# Interfaces_Isolation.net
KiCad netlist of a schematic drawn in Altium Designer
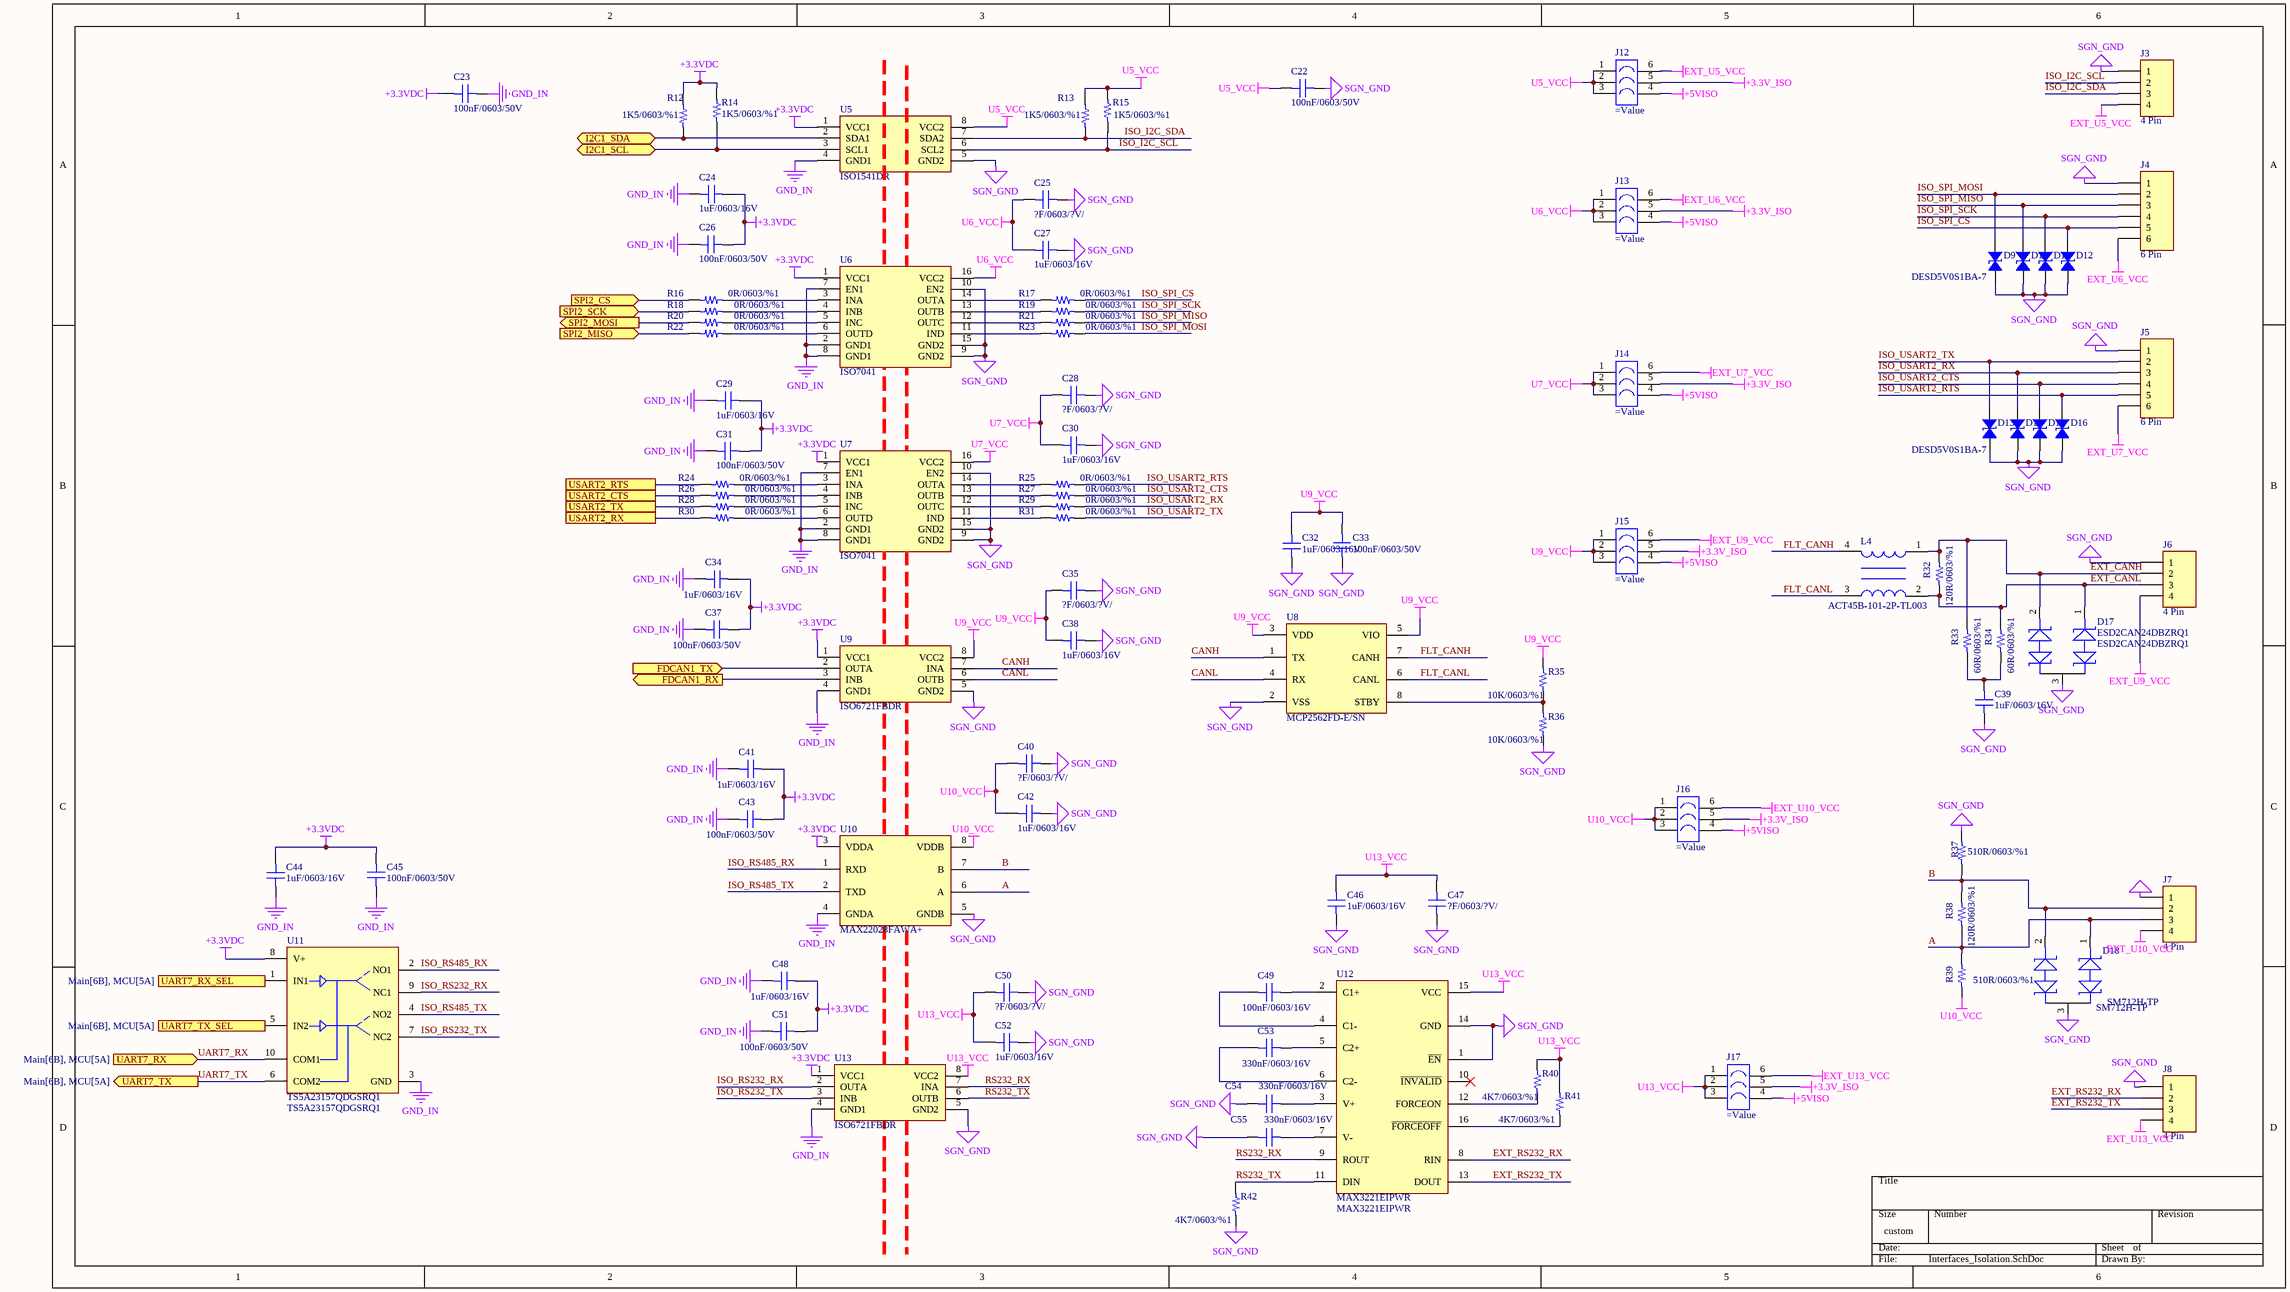
[diagram p0: Interfaces_Isolation.SchDoc]

(export (version "E")
  (design (tool "Eeschema 10.0.6"))
  (components
    (comp (ref "C22")
      (value "100nF/0603/50V")
      (footprint "0603_cap")
      (libsource (lib "IM_v1.0") (part "Capacitor"))
    )
    (comp (ref "C23")
      (value "100nF/0603/50V")
      (footprint "0603_cap")
      (libsource (lib "IM_v1.0") (part "Capacitor"))
    )
    (comp (ref "C24")
      (value "1uF/0603/16V")
      (footprint "0603_cap")
      (libsource (lib "IM_v1.0") (part "Capacitor"))
    )
    (comp (ref "C25")
      (value "?F/0603/?V/")
      (footprint "0603_cap")
      (libsource (lib "IM_v1.0") (part "Capacitor"))
    )
    (comp (ref "C26")
      (value "100nF/0603/50V")
      (footprint "0603_cap")
      (libsource (lib "IM_v1.0") (part "Capacitor"))
    )
    (comp (ref "C27")
      (value "1uF/0603/16V")
      (footprint "0603_cap")
      (libsource (lib "IM_v1.0") (part "Capacitor"))
    )
    (comp (ref "C28")
      (value "?F/0603/?V/")
      (footprint "0603_cap")
      (libsource (lib "IM_v1.0") (part "Capacitor"))
    )
    (comp (ref "C29")
      (value "1uF/0603/16V")
      (footprint "0603_cap")
      (libsource (lib "IM_v1.0") (part "Capacitor"))
    )
    (comp (ref "C30")
      (value "1uF/0603/16V")
      (footprint "0603_cap")
      (libsource (lib "IM_v1.0") (part "Capacitor"))
    )
    (comp (ref "C31")
      (value "100nF/0603/50V")
      (footprint "0603_cap")
      (libsource (lib "IM_v1.0") (part "Capacitor"))
    )
    (comp (ref "C32")
      (value "1uF/0603/16V")
      (footprint "0603_cap")
      (libsource (lib "IM_v1.0") (part "Capacitor"))
    )
    (comp (ref "C33")
      (value "100nF/0603/50V")
      (footprint "0603_cap")
      (libsource (lib "IM_v1.0") (part "Capacitor"))
    )
    (comp (ref "C34")
      (value "1uF/0603/16V")
      (footprint "0603_cap")
      (libsource (lib "IM_v1.0") (part "Capacitor"))
    )
    (comp (ref "C35")
      (value "?F/0603/?V/")
      (footprint "0603_cap")
      (libsource (lib "IM_v1.0") (part "Capacitor"))
    )
    (comp (ref "C37")
      (value "100nF/0603/50V")
      (footprint "0603_cap")
      (libsource (lib "IM_v1.0") (part "Capacitor"))
    )
    (comp (ref "C38")
      (value "1uF/0603/16V")
      (footprint "0603_cap")
      (libsource (lib "IM_v1.0") (part "Capacitor"))
    )
    (comp (ref "C39")
      (value "1uF/0603/16V")
      (footprint "0603_cap")
      (libsource (lib "IM_v1.0") (part "Capacitor"))
    )
    (comp (ref "C40")
      (value "?F/0603/?V/")
      (footprint "0603_cap")
      (libsource (lib "IM_v1.0") (part "Capacitor"))
    )
    (comp (ref "C41")
      (value "1uF/0603/16V")
      (footprint "0603_cap")
      (libsource (lib "IM_v1.0") (part "Capacitor"))
    )
    (comp (ref "C42")
      (value "1uF/0603/16V")
      (footprint "0603_cap")
      (libsource (lib "IM_v1.0") (part "Capacitor"))
    )
    (comp (ref "C43")
      (value "100nF/0603/50V")
      (footprint "0603_cap")
      (libsource (lib "IM_v1.0") (part "Capacitor"))
    )
    (comp (ref "C44")
      (value "1uF/0603/16V")
      (footprint "0603_cap")
      (libsource (lib "IM_v1.0") (part "Capacitor"))
    )
    (comp (ref "C45")
      (value "100nF/0603/50V")
      (footprint "0603_cap")
      (libsource (lib "IM_v1.0") (part "Capacitor"))
    )
    (comp (ref "C46")
      (value "1uF/0603/16V")
      (footprint "0603_cap")
      (libsource (lib "IM_v1.0") (part "Capacitor"))
    )
    (comp (ref "C47")
      (value "?F/0603/?V/")
      (footprint "0603_cap")
      (libsource (lib "IM_v1.0") (part "Capacitor"))
    )
    (comp (ref "C48")
      (value "1uF/0603/16V")
      (footprint "0603_cap")
      (libsource (lib "IM_v1.0") (part "Capacitor"))
    )
    (comp (ref "C49")
      (value "100nF/0603/16V")
      (footprint "0603_cap")
      (libsource (lib "IM_v1.0") (part "Capacitor"))
    )
    (comp (ref "C50")
      (value "?F/0603/?V/")
      (footprint "0603_cap")
      (libsource (lib "IM_v1.0") (part "Capacitor"))
    )
    (comp (ref "C51")
      (value "100nF/0603/50V")
      (footprint "0603_cap")
      (libsource (lib "IM_v1.0") (part "Capacitor"))
    )
    (comp (ref "C52")
      (value "1uF/0603/16V")
      (footprint "0603_cap")
      (libsource (lib "IM_v1.0") (part "Capacitor"))
    )
    (comp (ref "C53")
      (value "330nF/0603/16V")
      (footprint "0603_cap")
      (libsource (lib "IM_v1.0") (part "Capacitor"))
    )
    (comp (ref "C54")
      (value "330nF/0603/16V")
      (footprint "0603_cap")
      (libsource (lib "IM_v1.0") (part "Capacitor"))
    )
    (comp (ref "C55")
      (value "330nF/0603/16V")
      (footprint "0603_cap")
      (libsource (lib "IM_v1.0") (part "Capacitor"))
    )
    (comp (ref "D9")
      (value "DESD5V0S1BA-7")
      (footprint "SOD323")
      (description "Zener Diode")
      (libsource (lib "IM_v1.0") (part "TVS BI"))
    )
    (comp (ref "D10")
      (value "DESD5V0S1BA-7")
      (footprint "SOD323")
      (description "Zener Diode")
      (libsource (lib "IM_v1.0") (part "TVS BI"))
    )
    (comp (ref "D11")
      (value "DESD5V0S1BA-7")
      (footprint "SOD323")
      (description "Zener Diode")
      (libsource (lib "IM_v1.0") (part "TVS BI"))
    )
    (comp (ref "D12")
      (value "DESD5V0S1BA-7")
      (footprint "SOD323")
      (description "Zener Diode")
      (libsource (lib "IM_v1.0") (part "TVS BI"))
    )
    (comp (ref "D13")
      (value "DESD5V0S1BA-7")
      (footprint "SOD323")
      (description "Zener Diode")
      (libsource (lib "IM_v1.0") (part "TVS BI"))
    )
    (comp (ref "D14")
      (value "DESD5V0S1BA-7")
      (footprint "SOD323")
      (description "Zener Diode")
      (libsource (lib "IM_v1.0") (part "TVS BI"))
    )
    (comp (ref "D15")
      (value "DESD5V0S1BA-7")
      (footprint "SOD323")
      (description "Zener Diode")
      (libsource (lib "IM_v1.0") (part "TVS BI"))
    )
    (comp (ref "D16")
      (value "DESD5V0S1BA-7")
      (footprint "SOD323")
      (description "Zener Diode")
      (libsource (lib "IM_v1.0") (part "TVS BI"))
    )
    (comp (ref "D17")
      (value "ESD2CAN24DBZRQ1")
      (footprint "TI SOT-23-3 DBZ")
      (description "37V (Typ) Clamp 5.7A (8/20µs) Ipp Tvs Diode Surface Mount SOT-23-3")
      (fields (field (name "ALTIUM_VALUE") "ESD2CAN24DBZRQ1"))
      (libsource (lib "IM_v1.0") (part "SM712H-TP"))
    )
    (comp (ref "D18")
      (value "SM712H-TP")
      (footprint "TI SOT-23-3 DBZ")
      (description "TVS DIODE 12VWM 28VC SOT23")
      (fields (field (name "ALTIUM_VALUE") "SM712H-TP"))
      (libsource (lib "IM_v1.0") (part "SM712H-TP"))
    )
    (comp (ref "J3")
      (value "4 Pin")
      (footprint "R/A HEADER (4PİN)")
      (libsource (lib "IM_v1.0") (part "4 Pin"))
    )
    (comp (ref "J4") (value "6 Pin") (footprint "R/A HEADER") (libsource (lib "IM_v1.0") (part "6 Pin")))
    (comp (ref "J5") (value "6 Pin") (footprint "R/A HEADER") (libsource (lib "IM_v1.0") (part "6 Pin")))
    (comp (ref "J6")
      (value "4 Pin")
      (footprint "R/A HEADER (4PİN)")
      (libsource (lib "IM_v1.0") (part "4 Pin"))
    )
    (comp (ref "J7")
      (value "4 Pin")
      (footprint "R/A HEADER (4PİN)")
      (libsource (lib "IM_v1.0") (part "4 Pin"))
    )
    (comp (ref "J8")
      (value "4 Pin")
      (footprint "R/A HEADER (4PİN)")
      (libsource (lib "IM_v1.0") (part "4 Pin"))
    )
    (comp (ref "J12")
      (value "~")
      (footprint "th_ra_6pins_1.27mm")
      (libsource (lib "IM_v1.0") (part "2x3_header"))
    )
    (comp (ref "J13")
      (value "~")
      (footprint "th_ra_6pins_1.27mm")
      (libsource (lib "IM_v1.0") (part "2x3_header"))
    )
    (comp (ref "J14")
      (value "~")
      (footprint "th_ra_6pins_1.27mm")
      (libsource (lib "IM_v1.0") (part "2x3_header"))
    )
    (comp (ref "J15")
      (value "~")
      (footprint "th_ra_6pins_1.27mm")
      (libsource (lib "IM_v1.0") (part "2x3_header"))
    )
    (comp (ref "J16")
      (value "~")
      (footprint "th_ra_6pins_1.27mm")
      (libsource (lib "IM_v1.0") (part "2x3_header"))
    )
    (comp (ref "J17")
      (value "~")
      (footprint "th_ra_6pins_1.27mm")
      (libsource (lib "IM_v1.0") (part "2x3_header"))
    )
    (comp (ref "L4")
      (value "ACT45B-101-2P-TL003")
      (footprint "CMC((4.50mm x 3.20mm))")
      (description "100 µH @ 100 kHz 2 Line Common Mode Choke Surface Mount 5.8 kOhms @ 10 MHz 150mA DCR 2Ohm")
      (libsource (lib "IM_v1.0") (part "cmc"))
    )
    (comp (ref "R12") (value "1K5/0603/%1") (footprint "0603_res") (libsource (lib "IM_v1.0") (part "RES")))
    (comp (ref "R13") (value "1K5/0603/%1") (footprint "0603_res") (libsource (lib "IM_v1.0") (part "RES")))
    (comp (ref "R14") (value "1K5/0603/%1") (footprint "0603_res") (libsource (lib "IM_v1.0") (part "RES")))
    (comp (ref "R15") (value "1K5/0603/%1") (footprint "0603_res") (libsource (lib "IM_v1.0") (part "RES")))
    (comp (ref "R16") (value "0R/0603/%1") (footprint "0603_res") (libsource (lib "IM_v1.0") (part "RES")))
    (comp (ref "R17") (value "0R/0603/%1") (footprint "0603_res") (libsource (lib "IM_v1.0") (part "RES")))
    (comp (ref "R18") (value "0R/0603/%1") (footprint "0603_res") (libsource (lib "IM_v1.0") (part "RES")))
    (comp (ref "R19") (value "0R/0603/%1") (footprint "0603_res") (libsource (lib "IM_v1.0") (part "RES")))
    (comp (ref "R20") (value "0R/0603/%1") (footprint "0603_res") (libsource (lib "IM_v1.0") (part "RES")))
    (comp (ref "R21") (value "0R/0603/%1") (footprint "0603_res") (libsource (lib "IM_v1.0") (part "RES")))
    (comp (ref "R22") (value "0R/0603/%1") (footprint "0603_res") (libsource (lib "IM_v1.0") (part "RES")))
    (comp (ref "R23") (value "0R/0603/%1") (footprint "0603_res") (libsource (lib "IM_v1.0") (part "RES")))
    (comp (ref "R24") (value "0R/0603/%1") (footprint "0603_res") (libsource (lib "IM_v1.0") (part "RES")))
    (comp (ref "R25") (value "0R/0603/%1") (footprint "0603_res") (libsource (lib "IM_v1.0") (part "RES")))
    (comp (ref "R26") (value "0R/0603/%1") (footprint "0603_res") (libsource (lib "IM_v1.0") (part "RES")))
    (comp (ref "R27") (value "0R/0603/%1") (footprint "0603_res") (libsource (lib "IM_v1.0") (part "RES")))
    (comp (ref "R28") (value "0R/0603/%1") (footprint "0603_res") (libsource (lib "IM_v1.0") (part "RES")))
    (comp (ref "R29") (value "0R/0603/%1") (footprint "0603_res") (libsource (lib "IM_v1.0") (part "RES")))
    (comp (ref "R30") (value "0R/0603/%1") (footprint "0603_res") (libsource (lib "IM_v1.0") (part "RES")))
    (comp (ref "R31") (value "0R/0603/%1") (footprint "0603_res") (libsource (lib "IM_v1.0") (part "RES")))
    (comp (ref "R32") (value "120R/0603/%1") (footprint "0603_res") (libsource (lib "IM_v1.0") (part "RES")))
    (comp (ref "R33") (value "60R/0603/%1") (footprint "0603_res") (libsource (lib "IM_v1.0") (part "RES")))
    (comp (ref "R34") (value "60R/0603/%1") (footprint "0603_res") (libsource (lib "IM_v1.0") (part "RES")))
    (comp (ref "R35") (value "10K/0603/%1") (footprint "0603_res") (libsource (lib "IM_v1.0") (part "RES")))
    (comp (ref "R36") (value "10K/0603/%1") (footprint "0603_res") (libsource (lib "IM_v1.0") (part "RES")))
    (comp (ref "R37") (value "510R/0603/%1") (footprint "0603_res") (libsource (lib "IM_v1.0") (part "RES")))
    (comp (ref "R38") (value "120R/0603/%1") (footprint "0603_res") (libsource (lib "IM_v1.0") (part "RES")))
    (comp (ref "R39") (value "510R/0603/%1") (footprint "0603_res") (libsource (lib "IM_v1.0") (part "RES")))
    (comp (ref "R40") (value "4K7/0603/%1") (footprint "0603_res") (libsource (lib "IM_v1.0") (part "RES")))
    (comp (ref "R41") (value "4K7/0603/%1") (footprint "0603_res") (libsource (lib "IM_v1.0") (part "RES")))
    (comp (ref "R42") (value "4K7/0603/%1") (footprint "0603_res") (libsource (lib "IM_v1.0") (part "RES")))
    (comp (ref "U5")
      (value "ISO1541DR")
      (footprint "SOIC-8(3.90MM)")
      (description "I2C Digital Isolator 2500Vrms 2 Channel 1Mbps 25kV/µs CMTI 8-SOIC (0.154\", 3.90mm Width)")
      (libsource (lib "IM_v1.0") (part "TI ISO154x"))
    )
    (comp (ref "U6")
      (value "ISO7041")
      (footprint "16-SSOP (0.154\", 3.90mm Width)")
      (description "SPI Digital Isolator 3000Vrms 4 Channel 2Mbps 50kV/µs CMTI 16-SSOP (0.154\", 3.90mm Width)")
      (libsource (lib "IM_v1.0") (part "ISO7041"))
    )
    (comp (ref "U7")
      (value "ISO7041")
      (footprint "16-SSOP (0.154\", 3.90mm Width)")
      (description "SPI Digital Isolator 3000Vrms 4 Channel 2Mbps 50kV/µs CMTI 16-SSOP (0.154\", 3.90mm Width)")
      (libsource (lib "IM_v1.0") (part "ISO7041"))
    )
    (comp (ref "U8")
      (value "MCP2562FD-E/SN")
      (footprint "SOIC-8(3.90MM)")
      (description "1/1 Transceiver CANbus 8-SOIC")
      (libsource (lib "IM_v1.0") (part "MCP2562FD-E/SN"))
    )
    (comp (ref "U9")
      (value "ISO6721FBDR")
      (footprint "SOIC-8(3.90MM)")
      (libsource (lib "IM_v1.0") (part "ISO6721FBDR"))
    )
    (comp (ref "U10")
      (value "MAX22028FAWA+")
      (footprint "8-SOIC (0.209\", 5.30mm Width)")
      (description "1/1 Transceiver, Isolated Half RS422, RS485 8-SOIC")
      (libsource (lib "IM_v1.0") (part "MAX22028FAWA+"))
    )
    (comp (ref "U11")
      (value "TS5A23157QDGSRQ1")
      (footprint "VSSOP-10")
      (description "IC SWITCH SPDT X 2 15OHM 10VSSOP")
      (fields (field (name "ALTIUM_VALUE") "TS5A23157QDGSRQ1"))
      (libsource (lib "IM_v1.0") (part "TS5A23157QDGSRQ1"))
    )
    (comp (ref "U12")
      (value "MAX3221EIPWR")
      (footprint "16-TSSOP")
      (description "IC TRANSCEIVER FULL 1/1 16TSSOP")
      (fields (field (name "ALTIUM_VALUE") "MAX3221EIPWR"))
      (libsource (lib "IM_v1.0") (part "MAX3221EIPWR"))
    )
    (comp (ref "U13")
      (value "ISO6721FBDR")
      (footprint "SOIC-8(3.90MM)")
      (libsource (lib "IM_v1.0") (part "ISO6721FBDR"))
    )
  )
  (nets
    (net (code "1") (name "+3.3VDC") (class "Default")
      (node (ref "C23") (pin "2") (pinfunction "2_2") (pintype "passive"))
      (node (ref "C24") (pin "2") (pinfunction "2_2") (pintype "passive"))
      (node (ref "C26") (pin "1") (pinfunction "1_1") (pintype "passive"))
      (node (ref "C29") (pin "2") (pinfunction "2_2") (pintype "passive"))
      (node (ref "C31") (pin "1") (pinfunction "1_1") (pintype "passive"))
      (node (ref "C34") (pin "2") (pinfunction "2_2") (pintype "passive"))
      (node (ref "C37") (pin "1") (pinfunction "1_1") (pintype "passive"))
      (node (ref "C41") (pin "2") (pinfunction "2_2") (pintype "passive"))
      (node (ref "C43") (pin "1") (pinfunction "1_1") (pintype "passive"))
      (node (ref "C44") (pin "2") (pinfunction "2_2") (pintype "passive"))
      (node (ref "C45") (pin "1") (pinfunction "1_1") (pintype "passive"))
      (node (ref "C48") (pin "2") (pinfunction "2_2") (pintype "passive"))
      (node (ref "C51") (pin "1") (pinfunction "1_1") (pintype "passive"))
      (node (ref "R12") (pin "2") (pinfunction "2_2") (pintype "passive"))
      (node (ref "R14") (pin "1") (pinfunction "1_1") (pintype "passive"))
      (node (ref "U10") (pin "3") (pinfunction "VDDA_3") (pintype "passive"))
      (node (ref "U11") (pin "8") (pinfunction "V+_8") (pintype "passive"))
      (node (ref "U13") (pin "1") (pinfunction "VCC1_1") (pintype "passive"))
      (node (ref "U5") (pin "1") (pinfunction "VCC1_1") (pintype "passive"))
      (node (ref "U6") (pin "1") (pinfunction "VCC1_1") (pintype "passive"))
      (node (ref "U7") (pin "1") (pinfunction "VCC1_1") (pintype "passive"))
      (node (ref "U9") (pin "1") (pinfunction "VCC1_1") (pintype "passive"))
    )
    (net (code "2") (name "+3.3V_ISO") (class "Default")
      (node (ref "J12") (pin "5") (pinfunction "5_5") (pintype "passive"))
      (node (ref "J13") (pin "5") (pinfunction "5_5") (pintype "passive"))
      (node (ref "J14") (pin "5") (pinfunction "5_5") (pintype "passive"))
      (node (ref "J15") (pin "5") (pinfunction "5_5") (pintype "passive"))
      (node (ref "J16") (pin "5") (pinfunction "5_5") (pintype "passive"))
      (node (ref "J17") (pin "5") (pinfunction "5_5") (pintype "passive"))
    )
    (net (code "3") (name "+5VISO") (class "Default")
      (node (ref "J12") (pin "4") (pinfunction "4_4") (pintype "passive"))
      (node (ref "J13") (pin "4") (pinfunction "4_4") (pintype "passive"))
      (node (ref "J14") (pin "4") (pinfunction "4_4") (pintype "passive"))
      (node (ref "J15") (pin "4") (pinfunction "4_4") (pintype "passive"))
      (node (ref "J16") (pin "4") (pinfunction "4_4") (pintype "passive"))
      (node (ref "J17") (pin "4") (pinfunction "4_4") (pintype "passive"))
    )
    (net (code "4") (name "/A") (class "Default")
      (node (ref "D18") (pin "1") (pinfunction "1_1") (pintype "passive"))
      (node (ref "J7") (pin "3") (pinfunction "3_3") (pintype "passive"))
      (node (ref "R38") (pin "2") (pinfunction "2_2") (pintype "passive"))
      (node (ref "R39") (pin "1") (pinfunction "1_1") (pintype "passive"))
      (node (ref "U10") (pin "6") (pinfunction "A_6") (pintype "passive"))
    )
    (net (code "5") (name "/B") (class "Default")
      (node (ref "D18") (pin "2") (pinfunction "2_2") (pintype "passive"))
      (node (ref "J7") (pin "2") (pinfunction "2_2") (pintype "passive"))
      (node (ref "R37") (pin "2") (pinfunction "2_2") (pintype "passive"))
      (node (ref "R38") (pin "1") (pinfunction "1_1") (pintype "passive"))
      (node (ref "U10") (pin "7") (pinfunction "B_7") (pintype "passive"))
    )
    (net (code "6") (name "/CANH") (class "Default")
      (node (ref "U8") (pin "1") (pinfunction "TX_1") (pintype "passive"))
      (node (ref "U9") (pin "7") (pinfunction "INA_7") (pintype "passive"))
    )
    (net (code "7") (name "/CANL") (class "Default")
      (node (ref "U8") (pin "4") (pinfunction "RX_4") (pintype "passive"))
      (node (ref "U9") (pin "6") (pinfunction "OUTB_6") (pintype "passive"))
    )
    (net (code "8") (name "/EXT_CANH") (class "Default")
      (node (ref "D17") (pin "2") (pinfunction "2_2") (pintype "passive"))
      (node (ref "J6") (pin "2") (pinfunction "2_2") (pintype "passive"))
      (node (ref "L4") (pin "1") (pinfunction "1_1") (pintype "passive"))
      (node (ref "R32") (pin "1") (pinfunction "1_1") (pintype "passive"))
      (node (ref "R33") (pin "1") (pinfunction "1_1") (pintype "passive"))
    )
    (net (code "9") (name "/EXT_CANL") (class "Default")
      (node (ref "D17") (pin "1") (pinfunction "1_1") (pintype "passive"))
      (node (ref "J6") (pin "3") (pinfunction "3_3") (pintype "passive"))
      (node (ref "L4") (pin "2") (pinfunction "2_2") (pintype "passive"))
      (node (ref "R32") (pin "2") (pinfunction "2_2") (pintype "passive"))
      (node (ref "R34") (pin "1") (pinfunction "1_1") (pintype "passive"))
    )
    (net (code "10") (name "/EXT_RS232_RX") (class "Default")
      (node (ref "J8") (pin "2") (pinfunction "2_2") (pintype "passive"))
      (node (ref "U12") (pin "8") (pinfunction "RIN_8") (pintype "passive"))
    )
    (net (code "11") (name "/EXT_RS232_TX") (class "Default")
      (node (ref "J8") (pin "3") (pinfunction "3_3") (pintype "passive"))
      (node (ref "U12") (pin "13") (pinfunction "DOUT_13") (pintype "passive"))
    )
    (net (code "12") (name "/FDCAN1_RX") (class "Default")
      (node (ref "U9") (pin "3") (pinfunction "INB_3") (pintype "passive"))
    )
    (net (code "13") (name "/FDCAN1_TX") (class "Default")
      (node (ref "U9") (pin "2") (pinfunction "OUTA_2") (pintype "passive"))
    )
    (net (code "14") (name "/FLT_CANH") (class "Default")
      (node (ref "L4") (pin "4") (pinfunction "4_4") (pintype "passive"))
      (node (ref "U8") (pin "7") (pinfunction "CANH_7") (pintype "passive"))
    )
    (net (code "15") (name "/FLT_CANL") (class "Default")
      (node (ref "L4") (pin "3") (pinfunction "3_3") (pintype "passive"))
      (node (ref "U8") (pin "6") (pinfunction "CANL_6") (pintype "passive"))
    )
    (net (code "16") (name "/I2C1_SCL") (class "Default")
      (node (ref "R14") (pin "2") (pinfunction "2_2") (pintype "passive"))
      (node (ref "U5") (pin "3") (pinfunction "SCL1_3") (pintype "passive"))
    )
    (net (code "17") (name "/I2C1_SDA") (class "Default")
      (node (ref "R12") (pin "1") (pinfunction "1_1") (pintype "passive"))
      (node (ref "U5") (pin "2") (pinfunction "SDA1_2") (pintype "passive"))
    )
    (net (code "18") (name "/ISO_I2C_SCL") (class "Default")
      (node (ref "J3") (pin "2") (pinfunction "2_2") (pintype "passive"))
      (node (ref "R15") (pin "2") (pinfunction "2_2") (pintype "passive"))
      (node (ref "U5") (pin "6") (pinfunction "SCL2_6") (pintype "passive"))
    )
    (net (code "19") (name "/ISO_I2C_SDA") (class "Default")
      (node (ref "J3") (pin "3") (pinfunction "3_3") (pintype "passive"))
      (node (ref "R13") (pin "1") (pinfunction "1_1") (pintype "passive"))
      (node (ref "U5") (pin "7") (pinfunction "SDA2_7") (pintype "passive"))
    )
    (net (code "20") (name "/ISO_RS232_RX") (class "Default")
      (node (ref "U11") (pin "9") (pinfunction "NC1_9") (pintype "passive"))
      (node (ref "U13") (pin "2") (pinfunction "OUTA_2") (pintype "passive"))
    )
    (net (code "21") (name "/ISO_RS232_TX") (class "Default")
      (node (ref "U11") (pin "7") (pinfunction "NC2_7") (pintype "passive"))
      (node (ref "U13") (pin "3") (pinfunction "INB_3") (pintype "passive"))
    )
    (net (code "22") (name "/ISO_RS485_RX") (class "Default")
      (node (ref "U10") (pin "1") (pinfunction "RXD_1") (pintype "passive"))
      (node (ref "U11") (pin "2") (pinfunction "NO1_2") (pintype "passive"))
    )
    (net (code "23") (name "/ISO_RS485_TX") (class "Default")
      (node (ref "U10") (pin "2") (pinfunction "TXD_2") (pintype "passive"))
      (node (ref "U11") (pin "4") (pinfunction "NO2_4") (pintype "passive"))
    )
    (net (code "24") (name "/ISO_SPI_CS") (class "Default")
      (node (ref "D12") (pin "2") (pinfunction "2_2") (pintype "passive"))
      (node (ref "J4") (pin "5") (pinfunction "5_5") (pintype "passive"))
      (node (ref "R17") (pin "1") (pinfunction "1_1") (pintype "passive"))
    )
    (net (code "25") (name "/ISO_SPI_MISO") (class "Default")
      (node (ref "D10") (pin "2") (pinfunction "2_2") (pintype "passive"))
      (node (ref "J4") (pin "3") (pinfunction "3_3") (pintype "passive"))
      (node (ref "R21") (pin "1") (pinfunction "1_1") (pintype "passive"))
    )
    (net (code "26") (name "/ISO_SPI_MOSI") (class "Default")
      (node (ref "D9") (pin "2") (pinfunction "2_2") (pintype "passive"))
      (node (ref "J4") (pin "2") (pinfunction "2_2") (pintype "passive"))
      (node (ref "R23") (pin "1") (pinfunction "1_1") (pintype "passive"))
    )
    (net (code "27") (name "/ISO_SPI_SCK") (class "Default")
      (node (ref "D11") (pin "2") (pinfunction "2_2") (pintype "passive"))
      (node (ref "J4") (pin "4") (pinfunction "4_4") (pintype "passive"))
      (node (ref "R19") (pin "1") (pinfunction "1_1") (pintype "passive"))
    )
    (net (code "28") (name "/ISO_USART2_CTS") (class "Default")
      (node (ref "D15") (pin "2") (pinfunction "2_2") (pintype "passive"))
      (node (ref "J5") (pin "4") (pinfunction "4_4") (pintype "passive"))
      (node (ref "R27") (pin "1") (pinfunction "1_1") (pintype "passive"))
    )
    (net (code "29") (name "/ISO_USART2_RTS") (class "Default")
      (node (ref "D16") (pin "2") (pinfunction "2_2") (pintype "passive"))
      (node (ref "J5") (pin "5") (pinfunction "5_5") (pintype "passive"))
      (node (ref "R25") (pin "1") (pinfunction "1_1") (pintype "passive"))
    )
    (net (code "30") (name "/ISO_USART2_RX") (class "Default")
      (node (ref "D14") (pin "2") (pinfunction "2_2") (pintype "passive"))
      (node (ref "J5") (pin "3") (pinfunction "3_3") (pintype "passive"))
      (node (ref "R29") (pin "1") (pinfunction "1_1") (pintype "passive"))
    )
    (net (code "31") (name "/ISO_USART2_TX") (class "Default")
      (node (ref "D13") (pin "2") (pinfunction "2_2") (pintype "passive"))
      (node (ref "J5") (pin "2") (pinfunction "2_2") (pintype "passive"))
      (node (ref "R31") (pin "1") (pinfunction "1_1") (pintype "passive"))
    )
    (net (code "32") (name "/RS232_RX") (class "Default")
      (node (ref "U12") (pin "9") (pinfunction "ROUT_9") (pintype "passive"))
      (node (ref "U13") (pin "7") (pinfunction "INA_7") (pintype "passive"))
    )
    (net (code "33") (name "/RS232_TX") (class "Default")
      (node (ref "R42") (pin "1") (pinfunction "1_1") (pintype "passive"))
      (node (ref "U12") (pin "11") (pinfunction "DIN_11") (pintype "passive"))
      (node (ref "U13") (pin "6") (pinfunction "OUTB_6") (pintype "passive"))
    )
    (net (code "34") (name "/SPI2_CS") (class "Default")
      (node (ref "R16") (pin "2") (pinfunction "2_2") (pintype "passive"))
    )
    (net (code "35") (name "/SPI2_MISO") (class "Default")
      (node (ref "R22") (pin "2") (pinfunction "2_2") (pintype "passive"))
    )
    (net (code "36") (name "/SPI2_MOSI") (class "Default")
      (node (ref "R20") (pin "2") (pinfunction "2_2") (pintype "passive"))
    )
    (net (code "37") (name "/SPI2_SCK") (class "Default")
      (node (ref "R18") (pin "2") (pinfunction "2_2") (pintype "passive"))
    )
    (net (code "38") (name "/UART7_RX") (class "Default")
      (node (ref "U11") (pin "10") (pinfunction "COM1_10") (pintype "passive"))
    )
    (net (code "39") (name "/UART7_RX_SEL") (class "Default")
      (node (ref "U11") (pin "1") (pinfunction "IN1_1") (pintype "passive"))
    )
    (net (code "40") (name "/UART7_TX") (class "Default")
      (node (ref "U11") (pin "6") (pinfunction "COM2_6") (pintype "passive"))
    )
    (net (code "41") (name "/UART7_TX_SEL") (class "Default")
      (node (ref "U11") (pin "5") (pinfunction "IN2_5") (pintype "passive"))
    )
    (net (code "42") (name "/USART2_CTS") (class "Default")
      (node (ref "R26") (pin "2") (pinfunction "2_2") (pintype "passive"))
    )
    (net (code "43") (name "/USART2_RTS") (class "Default")
      (node (ref "R24") (pin "2") (pinfunction "2_2") (pintype "passive"))
    )
    (net (code "44") (name "/USART2_RX") (class "Default")
      (node (ref "R30") (pin "2") (pinfunction "2_2") (pintype "passive"))
    )
    (net (code "45") (name "/USART2_TX") (class "Default")
      (node (ref "R28") (pin "2") (pinfunction "2_2") (pintype "passive"))
    )
    (net (code "46") (name "EXT_U5_VCC") (class "Default")
      (node (ref "J12") (pin "6") (pinfunction "6_6") (pintype "passive"))
      (node (ref "J3") (pin "4") (pinfunction "4_4") (pintype "passive"))
    )
    (net (code "47") (name "EXT_U6_VCC") (class "Default")
      (node (ref "J13") (pin "6") (pinfunction "6_6") (pintype "passive"))
      (node (ref "J4") (pin "6") (pinfunction "6_6") (pintype "passive"))
    )
    (net (code "48") (name "EXT_U7_VCC") (class "Default")
      (node (ref "J14") (pin "6") (pinfunction "6_6") (pintype "passive"))
      (node (ref "J5") (pin "6") (pinfunction "6_6") (pintype "passive"))
    )
    (net (code "49") (name "EXT_U9_VCC") (class "Default")
      (node (ref "J15") (pin "6") (pinfunction "6_6") (pintype "passive"))
      (node (ref "J6") (pin "4") (pinfunction "4_4") (pintype "passive"))
    )
    (net (code "50") (name "EXT_U10_VCC") (class "Default")
      (node (ref "J16") (pin "6") (pinfunction "6_6") (pintype "passive"))
      (node (ref "J7") (pin "4") (pinfunction "4_4") (pintype "passive"))
    )
    (net (code "51") (name "EXT_U13_VCC") (class "Default")
      (node (ref "J17") (pin "6") (pinfunction "6_6") (pintype "passive"))
      (node (ref "J8") (pin "4") (pinfunction "4_4") (pintype "passive"))
    )
    (net (code "52") (name "GND_IN") (class "Default")
      (node (ref "C23") (pin "1") (pinfunction "1_1") (pintype "passive"))
      (node (ref "C24") (pin "1") (pinfunction "1_1") (pintype "passive"))
      (node (ref "C26") (pin "2") (pinfunction "2_2") (pintype "passive"))
      (node (ref "C29") (pin "1") (pinfunction "1_1") (pintype "passive"))
      (node (ref "C31") (pin "2") (pinfunction "2_2") (pintype "passive"))
      (node (ref "C34") (pin "1") (pinfunction "1_1") (pintype "passive"))
      (node (ref "C37") (pin "2") (pinfunction "2_2") (pintype "passive"))
      (node (ref "C41") (pin "1") (pinfunction "1_1") (pintype "passive"))
      (node (ref "C43") (pin "2") (pinfunction "2_2") (pintype "passive"))
      (node (ref "C44") (pin "1") (pinfunction "1_1") (pintype "passive"))
      (node (ref "C45") (pin "2") (pinfunction "2_2") (pintype "passive"))
      (node (ref "C48") (pin "1") (pinfunction "1_1") (pintype "passive"))
      (node (ref "C51") (pin "2") (pinfunction "2_2") (pintype "passive"))
      (node (ref "U10") (pin "4") (pinfunction "GNDA_4") (pintype "passive"))
      (node (ref "U11") (pin "3") (pinfunction "GND_3") (pintype "passive"))
      (node (ref "U13") (pin "4") (pinfunction "GND1_4") (pintype "passive"))
      (node (ref "U5") (pin "4") (pinfunction "GND1_4") (pintype "passive"))
      (node (ref "U6") (pin "2") (pinfunction "GND1_2") (pintype "passive"))
      (node (ref "U6") (pin "7") (pinfunction "EN1_7") (pintype "passive"))
      (node (ref "U6") (pin "8") (pinfunction "GND1_8") (pintype "passive"))
      (node (ref "U7") (pin "2") (pinfunction "GND1_2") (pintype "passive"))
      (node (ref "U7") (pin "7") (pinfunction "EN1_7") (pintype "passive"))
      (node (ref "U7") (pin "8") (pinfunction "GND1_8") (pintype "passive"))
      (node (ref "U9") (pin "4") (pinfunction "GND1_4") (pintype "passive"))
    )
    (net (code "53") (name "Net-(C39-Pad2)") (class "Default")
      (node (ref "C39") (pin "2") (pinfunction "2_2") (pintype "passive"))
      (node (ref "R33") (pin "2") (pinfunction "2_2") (pintype "passive"))
      (node (ref "R34") (pin "2") (pinfunction "2_2") (pintype "passive"))
    )
    (net (code "54") (name "Net-(U6-INA)") (class "Default")
      (node (ref "R16") (pin "1") (pinfunction "1_1") (pintype "passive"))
      (node (ref "U6") (pin "3") (pinfunction "INA_3") (pintype "passive"))
    )
    (net (code "55") (name "Net-(U6-INB)") (class "Default")
      (node (ref "R18") (pin "1") (pinfunction "1_1") (pintype "passive"))
      (node (ref "U6") (pin "4") (pinfunction "INB_4") (pintype "passive"))
    )
    (net (code "56") (name "Net-(U6-INC)") (class "Default")
      (node (ref "R20") (pin "1") (pinfunction "1_1") (pintype "passive"))
      (node (ref "U6") (pin "5") (pinfunction "INC_5") (pintype "passive"))
    )
    (net (code "57") (name "Net-(U6-IND)") (class "Default")
      (node (ref "R23") (pin "2") (pinfunction "2_2") (pintype "passive"))
      (node (ref "U6") (pin "11") (pinfunction "IND_11") (pintype "passive"))
    )
    (net (code "58") (name "Net-(U6-OUTA)") (class "Default")
      (node (ref "R17") (pin "2") (pinfunction "2_2") (pintype "passive"))
      (node (ref "U6") (pin "14") (pinfunction "OUTA_14") (pintype "passive"))
    )
    (net (code "59") (name "Net-(U6-OUTB)") (class "Default")
      (node (ref "R19") (pin "2") (pinfunction "2_2") (pintype "passive"))
      (node (ref "U6") (pin "13") (pinfunction "OUTB_13") (pintype "passive"))
    )
    (net (code "60") (name "Net-(U6-OUTC)") (class "Default")
      (node (ref "R21") (pin "2") (pinfunction "2_2") (pintype "passive"))
      (node (ref "U6") (pin "12") (pinfunction "OUTC_12") (pintype "passive"))
    )
    (net (code "61") (name "Net-(U6-OUTD)") (class "Default")
      (node (ref "R22") (pin "1") (pinfunction "1_1") (pintype "passive"))
      (node (ref "U6") (pin "6") (pinfunction "OUTD_6") (pintype "passive"))
    )
    (net (code "62") (name "Net-(U7-INA)") (class "Default")
      (node (ref "R24") (pin "1") (pinfunction "1_1") (pintype "passive"))
      (node (ref "U7") (pin "3") (pinfunction "INA_3") (pintype "passive"))
    )
    (net (code "63") (name "Net-(U7-INB)") (class "Default")
      (node (ref "R26") (pin "1") (pinfunction "1_1") (pintype "passive"))
      (node (ref "U7") (pin "4") (pinfunction "INB_4") (pintype "passive"))
    )
    (net (code "64") (name "Net-(U7-INC)") (class "Default")
      (node (ref "R28") (pin "1") (pinfunction "1_1") (pintype "passive"))
      (node (ref "U7") (pin "5") (pinfunction "INC_5") (pintype "passive"))
    )
    (net (code "65") (name "Net-(U7-IND)") (class "Default")
      (node (ref "R31") (pin "2") (pinfunction "2_2") (pintype "passive"))
      (node (ref "U7") (pin "11") (pinfunction "IND_11") (pintype "passive"))
    )
    (net (code "66") (name "Net-(U7-OUTA)") (class "Default")
      (node (ref "R25") (pin "2") (pinfunction "2_2") (pintype "passive"))
      (node (ref "U7") (pin "14") (pinfunction "OUTA_14") (pintype "passive"))
    )
    (net (code "67") (name "Net-(U7-OUTB)") (class "Default")
      (node (ref "R27") (pin "2") (pinfunction "2_2") (pintype "passive"))
      (node (ref "U7") (pin "13") (pinfunction "OUTB_13") (pintype "passive"))
    )
    (net (code "68") (name "Net-(U7-OUTC)") (class "Default")
      (node (ref "R29") (pin "2") (pinfunction "2_2") (pintype "passive"))
      (node (ref "U7") (pin "12") (pinfunction "OUTC_12") (pintype "passive"))
    )
    (net (code "69") (name "Net-(U7-OUTD)") (class "Default")
      (node (ref "R30") (pin "1") (pinfunction "1_1") (pintype "passive"))
      (node (ref "U7") (pin "6") (pinfunction "OUTD_6") (pintype "passive"))
    )
    (net (code "70") (name "Net-(U8-STBY)") (class "Default")
      (node (ref "R35") (pin "2") (pinfunction "2_2") (pintype "passive"))
      (node (ref "R36") (pin "1") (pinfunction "1_1") (pintype "passive"))
      (node (ref "U8") (pin "8") (pinfunction "STBY_8") (pintype "passive"))
    )
    (net (code "71") (name "Net-(U12-C1+)") (class "Default")
      (node (ref "C49") (pin "1") (pinfunction "1_1") (pintype "passive"))
      (node (ref "U12") (pin "2") (pinfunction "C1+_2") (pintype "passive"))
    )
    (net (code "72") (name "Net-(U12-C1-)") (class "Default")
      (node (ref "C49") (pin "2") (pinfunction "2_2") (pintype "passive"))
      (node (ref "U12") (pin "4") (pinfunction "C1-_4") (pintype "passive"))
    )
    (net (code "73") (name "Net-(U12-C2+)") (class "Default")
      (node (ref "C53") (pin "1") (pinfunction "1_1") (pintype "passive"))
      (node (ref "U12") (pin "5") (pinfunction "C2+_5") (pintype "passive"))
    )
    (net (code "74") (name "Net-(U12-C2-)") (class "Default")
      (node (ref "C53") (pin "2") (pinfunction "2_2") (pintype "passive"))
      (node (ref "U12") (pin "6") (pinfunction "C2-_6") (pintype "passive"))
    )
    (net (code "75") (name "Net-(U12-FORCEON)") (class "Default")
      (node (ref "R40") (pin "2") (pinfunction "2_2") (pintype "passive"))
      (node (ref "U12") (pin "12") (pinfunction "FORCEON_12") (pintype "passive"))
    )
    (net (code "76") (name "Net-(U12-V+)") (class "Default")
      (node (ref "C54") (pin "1") (pinfunction "1_1") (pintype "passive"))
      (node (ref "U12") (pin "3") (pinfunction "V+_3") (pintype "passive"))
    )
    (net (code "77") (name "Net-(U12-V-)") (class "Default")
      (node (ref "C55") (pin "1") (pinfunction "1_1") (pintype "passive"))
      (node (ref "U12") (pin "7") (pinfunction "V-_7") (pintype "passive"))
    )
    (net (code "78") (name "Net-(U12-~{FORCEOFF})") (class "Default")
      (node (ref "R41") (pin "2") (pinfunction "2_2") (pintype "passive"))
      (node (ref "U12") (pin "16") (pinfunction "~{FORCEOFF}_16") (pintype "passive"))
    )
    (net (code "79") (name "SGN_GND") (class "Default")
      (node (ref "C22") (pin "1") (pinfunction "1_1") (pintype "passive"))
      (node (ref "C25") (pin "1") (pinfunction "1_1") (pintype "passive"))
      (node (ref "C27") (pin "1") (pinfunction "1_1") (pintype "passive"))
      (node (ref "C28") (pin "1") (pinfunction "1_1") (pintype "passive"))
      (node (ref "C30") (pin "1") (pinfunction "1_1") (pintype "passive"))
      (node (ref "C32") (pin "1") (pinfunction "1_1") (pintype "passive"))
      (node (ref "C33") (pin "2") (pinfunction "2_2") (pintype "passive"))
      (node (ref "C35") (pin "1") (pinfunction "1_1") (pintype "passive"))
      (node (ref "C38") (pin "1") (pinfunction "1_1") (pintype "passive"))
      (node (ref "C39") (pin "1") (pinfunction "1_1") (pintype "passive"))
      (node (ref "C40") (pin "1") (pinfunction "1_1") (pintype "passive"))
      (node (ref "C42") (pin "1") (pinfunction "1_1") (pintype "passive"))
      (node (ref "C46") (pin "1") (pinfunction "1_1") (pintype "passive"))
      (node (ref "C47") (pin "1") (pinfunction "1_1") (pintype "passive"))
      (node (ref "C50") (pin "1") (pinfunction "1_1") (pintype "passive"))
      (node (ref "C52") (pin "1") (pinfunction "1_1") (pintype "passive"))
      (node (ref "C54") (pin "2") (pinfunction "2_2") (pintype "passive"))
      (node (ref "C55") (pin "2") (pinfunction "2_2") (pintype "passive"))
      (node (ref "D10") (pin "1") (pinfunction "1_1") (pintype "passive"))
      (node (ref "D11") (pin "1") (pinfunction "1_1") (pintype "passive"))
      (node (ref "D12") (pin "1") (pinfunction "1_1") (pintype "passive"))
      (node (ref "D13") (pin "1") (pinfunction "1_1") (pintype "passive"))
      (node (ref "D14") (pin "1") (pinfunction "1_1") (pintype "passive"))
      (node (ref "D15") (pin "1") (pinfunction "1_1") (pintype "passive"))
      (node (ref "D16") (pin "1") (pinfunction "1_1") (pintype "passive"))
      (node (ref "D17") (pin "3") (pinfunction "3_3") (pintype "passive"))
      (node (ref "D18") (pin "3") (pinfunction "3_3") (pintype "passive"))
      (node (ref "D9") (pin "1") (pinfunction "1_1") (pintype "passive"))
      (node (ref "J3") (pin "1") (pinfunction "1_1") (pintype "passive"))
      (node (ref "J4") (pin "1") (pinfunction "1_1") (pintype "passive"))
      (node (ref "J5") (pin "1") (pinfunction "1_1") (pintype "passive"))
      (node (ref "J6") (pin "1") (pinfunction "1_1") (pintype "passive"))
      (node (ref "J7") (pin "1") (pinfunction "1_1") (pintype "passive"))
      (node (ref "J8") (pin "1") (pinfunction "1_1") (pintype "passive"))
      (node (ref "R36") (pin "2") (pinfunction "2_2") (pintype "passive"))
      (node (ref "R37") (pin "1") (pinfunction "1_1") (pintype "passive"))
      (node (ref "R42") (pin "2") (pinfunction "2_2") (pintype "passive"))
      (node (ref "U10") (pin "5") (pinfunction "GNDB_5") (pintype "passive"))
      (node (ref "U12") (pin "1") (pinfunction "~{EN}_1") (pintype "passive"))
      (node (ref "U12") (pin "14") (pinfunction "GND_14") (pintype "passive"))
      (node (ref "U13") (pin "5") (pinfunction "GND2_5") (pintype "passive"))
      (node (ref "U5") (pin "5") (pinfunction "GND2_5") (pintype "passive"))
      (node (ref "U6") (pin "10") (pinfunction "EN2_10") (pintype "passive"))
      (node (ref "U6") (pin "15") (pinfunction "GND2_15") (pintype "passive"))
      (node (ref "U6") (pin "9") (pinfunction "GND2_9") (pintype "passive"))
      (node (ref "U7") (pin "10") (pinfunction "EN2_10") (pintype "passive"))
      (node (ref "U7") (pin "15") (pinfunction "GND2_15") (pintype "passive"))
      (node (ref "U7") (pin "9") (pinfunction "GND2_9") (pintype "passive"))
      (node (ref "U8") (pin "2") (pinfunction "VSS_2") (pintype "passive"))
      (node (ref "U9") (pin "5") (pinfunction "GND2_5") (pintype "passive"))
    )
    (net (code "80") (name "U5_VCC") (class "Default")
      (node (ref "C22") (pin "2") (pinfunction "2_2") (pintype "passive"))
      (node (ref "J12") (pin "1") (pinfunction "1_1") (pintype "passive"))
      (node (ref "J12") (pin "2") (pinfunction "2_2") (pintype "passive"))
      (node (ref "J12") (pin "3") (pinfunction "3_3") (pintype "passive"))
      (node (ref "R13") (pin "2") (pinfunction "2_2") (pintype "passive"))
      (node (ref "R15") (pin "1") (pinfunction "1_1") (pintype "passive"))
      (node (ref "U5") (pin "8") (pinfunction "VCC2_8") (pintype "passive"))
    )
    (net (code "81") (name "U6_VCC") (class "Default")
      (node (ref "C25") (pin "2") (pinfunction "2_2") (pintype "passive"))
      (node (ref "C27") (pin "2") (pinfunction "2_2") (pintype "passive"))
      (node (ref "J13") (pin "1") (pinfunction "1_1") (pintype "passive"))
      (node (ref "J13") (pin "2") (pinfunction "2_2") (pintype "passive"))
      (node (ref "J13") (pin "3") (pinfunction "3_3") (pintype "passive"))
      (node (ref "U6") (pin "16") (pinfunction "VCC2_16") (pintype "passive"))
    )
    (net (code "82") (name "U7_VCC") (class "Default")
      (node (ref "C28") (pin "2") (pinfunction "2_2") (pintype "passive"))
      (node (ref "C30") (pin "2") (pinfunction "2_2") (pintype "passive"))
      (node (ref "J14") (pin "1") (pinfunction "1_1") (pintype "passive"))
      (node (ref "J14") (pin "2") (pinfunction "2_2") (pintype "passive"))
      (node (ref "J14") (pin "3") (pinfunction "3_3") (pintype "passive"))
      (node (ref "U7") (pin "16") (pinfunction "VCC2_16") (pintype "passive"))
    )
    (net (code "83") (name "U9_VCC") (class "Default")
      (node (ref "C32") (pin "2") (pinfunction "2_2") (pintype "passive"))
      (node (ref "C33") (pin "1") (pinfunction "1_1") (pintype "passive"))
      (node (ref "C35") (pin "2") (pinfunction "2_2") (pintype "passive"))
      (node (ref "C38") (pin "2") (pinfunction "2_2") (pintype "passive"))
      (node (ref "J15") (pin "1") (pinfunction "1_1") (pintype "passive"))
      (node (ref "J15") (pin "2") (pinfunction "2_2") (pintype "passive"))
      (node (ref "J15") (pin "3") (pinfunction "3_3") (pintype "passive"))
      (node (ref "R35") (pin "1") (pinfunction "1_1") (pintype "passive"))
      (node (ref "U8") (pin "3") (pinfunction "VDD_3") (pintype "passive"))
      (node (ref "U8") (pin "5") (pinfunction "VIO_5") (pintype "passive"))
      (node (ref "U9") (pin "8") (pinfunction "VCC2_8") (pintype "passive"))
    )
    (net (code "84") (name "U10_VCC") (class "Default")
      (node (ref "C40") (pin "2") (pinfunction "2_2") (pintype "passive"))
      (node (ref "C42") (pin "2") (pinfunction "2_2") (pintype "passive"))
      (node (ref "J16") (pin "1") (pinfunction "1_1") (pintype "passive"))
      (node (ref "J16") (pin "2") (pinfunction "2_2") (pintype "passive"))
      (node (ref "J16") (pin "3") (pinfunction "3_3") (pintype "passive"))
      (node (ref "R39") (pin "2") (pinfunction "2_2") (pintype "passive"))
      (node (ref "U10") (pin "8") (pinfunction "VDDB_8") (pintype "passive"))
    )
    (net (code "85") (name "U13_VCC") (class "Default")
      (node (ref "C46") (pin "2") (pinfunction "2_2") (pintype "passive"))
      (node (ref "C47") (pin "2") (pinfunction "2_2") (pintype "passive"))
      (node (ref "C50") (pin "2") (pinfunction "2_2") (pintype "passive"))
      (node (ref "C52") (pin "2") (pinfunction "2_2") (pintype "passive"))
      (node (ref "J17") (pin "1") (pinfunction "1_1") (pintype "passive"))
      (node (ref "J17") (pin "2") (pinfunction "2_2") (pintype "passive"))
      (node (ref "J17") (pin "3") (pinfunction "3_3") (pintype "passive"))
      (node (ref "R40") (pin "1") (pinfunction "1_1") (pintype "passive"))
      (node (ref "R41") (pin "1") (pinfunction "1_1") (pintype "passive"))
      (node (ref "U12") (pin "15") (pinfunction "VCC_15") (pintype "passive"))
      (node (ref "U13") (pin "8") (pinfunction "VCC2_8") (pintype "passive"))
    )
    (net (code "86") (name "unconnected-(U12-~{INVALID}-Pad10)") (class "Default")
      (node (ref "U12") (pin "10") (pinfunction "~{INVALID}_10") (pintype "passive+no_connect"))
    )
  )
)
